# Mako_DSP_USB_R2_0.net
KiCad netlist of a schematic drawn in Altium Designer
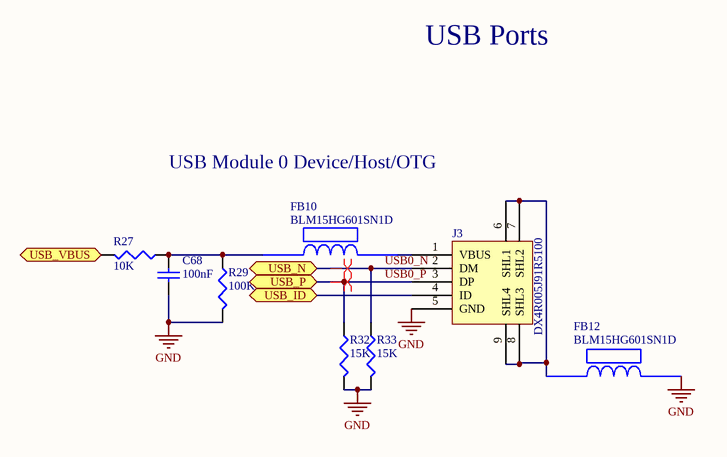
[diagram p0: Mako DSP USB R2.0.SchDoc]

(export (version "E")
  (design (tool "Eeschema 10.0.6"))
  (components
    (comp (ref "C68")
      (value "100nF")
      (footprint "1608[0603]")
      (description "Capacitor (Semiconductor SIM Model)")
      (fields (field (name "Comment") "Cap Semi") (field (name "PUBLISHER") "Altium Limited"))
      (libsource (lib "Miscellaneous Devices") (part "Cap Semi"))
    )
    (comp (ref "FB10")
      (value "BLM15HG601SN1D")
      (footprint "BLM18PG121SN1D")
      (libsource (lib "AHD Part Library") (part "BLM15HG601SN1D"))
    )
    (comp (ref "FB12")
      (value "BLM15HG601SN1D")
      (footprint "BLM18PG121SN1D")
      (libsource (lib "AHD Part Library") (part "BLM15HG601SN1D"))
    )
    (comp (ref "J3")
      (value "DX4R005J91R5100")
      (footprint "Micro USB Circular Holes Only")
      (description "Micro USB Jack B")
      (libsource (lib "Adams Altium Library") (part "Micro USB"))
    )
    (comp (ref "R27")
      (value "10K")
      (footprint "J1-0603")
      (description "Resistor")
      (fields (field (name "Comment") "Res3") (field (name "PUBLISHER") "Altium Limited"))
      (libsource (lib "Miscellaneous Devices") (part "Res3"))
    )
    (comp (ref "R29")
      (value "100K")
      (footprint "J1-0603")
      (description "Resistor")
      (fields (field (name "Comment") "Res3") (field (name "PUBLISHER") "Altium Limited"))
      (libsource (lib "Miscellaneous Devices") (part "Res3"))
    )
    (comp (ref "R32")
      (value "15K")
      (footprint "J1-0603")
      (description "Resistor")
      (fields (field (name "Comment") "Res3") (field (name "PUBLISHER") "Altium Limited"))
      (libsource (lib "Miscellaneous Devices") (part "Res3"))
    )
    (comp (ref "R33")
      (value "15K")
      (footprint "J1-0603")
      (description "Resistor")
      (fields (field (name "Comment") "Res3") (field (name "PUBLISHER") "Altium Limited"))
      (libsource (lib "Miscellaneous Devices") (part "Res3"))
    )
  )
  (nets
    (net (code "1") (name "/USB0_N") (class "Default")
      (node (ref "J3") (pin "2") (pinfunction "DM_2") (pintype "passive"))
      (node (ref "R33") (pin "1") (pinfunction "1_1") (pintype "passive"))
    )
    (net (code "2") (name "/USB0_P") (class "Default")
      (node (ref "J3") (pin "3") (pinfunction "DP_3") (pintype "passive"))
      (node (ref "R32") (pin "1") (pinfunction "1_1") (pintype "passive"))
    )
    (net (code "3") (name "/USB_ID") (class "Default")
      (node (ref "J3") (pin "4") (pinfunction "ID_4") (pintype "passive"))
    )
    (net (code "4") (name "/USB_VBUS") (class "Default")
      (node (ref "R27") (pin "2") (pinfunction "2_2") (pintype "passive"))
    )
    (net (code "5") (name "GND") (class "Default")
      (node (ref "C68") (pin "1") (pinfunction "1_1") (pintype "passive"))
      (node (ref "FB12") (pin "2") (pinfunction "2_2") (pintype "passive"))
      (node (ref "J3") (pin "5") (pinfunction "GND_5") (pintype "passive"))
      (node (ref "R29") (pin "2") (pinfunction "2_2") (pintype "passive"))
      (node (ref "R32") (pin "2") (pinfunction "2_2") (pintype "passive"))
      (node (ref "R33") (pin "2") (pinfunction "2_2") (pintype "passive"))
    )
    (net (code "6") (name "Net-(C68-Pad2)") (class "Default")
      (node (ref "C68") (pin "2") (pinfunction "2_2") (pintype "passive"))
      (node (ref "FB10") (pin "1") (pinfunction "1_1") (pintype "passive"))
      (node (ref "R27") (pin "1") (pinfunction "1_1") (pintype "passive"))
      (node (ref "R29") (pin "1") (pinfunction "1_1") (pintype "passive"))
    )
    (net (code "7") (name "Net-(J3-SHL1)") (class "Default")
      (node (ref "FB12") (pin "1") (pinfunction "1_1") (pintype "passive"))
      (node (ref "J3") (pin "6") (pinfunction "SHL1_6") (pintype "passive"))
      (node (ref "J3") (pin "7") (pinfunction "SHL2_7") (pintype "passive"))
      (node (ref "J3") (pin "8") (pinfunction "SHL3_8") (pintype "passive"))
      (node (ref "J3") (pin "9") (pinfunction "SHL4_9") (pintype "passive"))
    )
    (net (code "8") (name "Net-(J3-VBUS)") (class "Default")
      (node (ref "FB10") (pin "2") (pinfunction "2_2") (pintype "passive"))
      (node (ref "J3") (pin "1") (pinfunction "VBUS_1") (pintype "passive"))
    )
  )
)
